# ngh-ioctl.net
KiCad netlist of a schematic drawn in Altium Designer
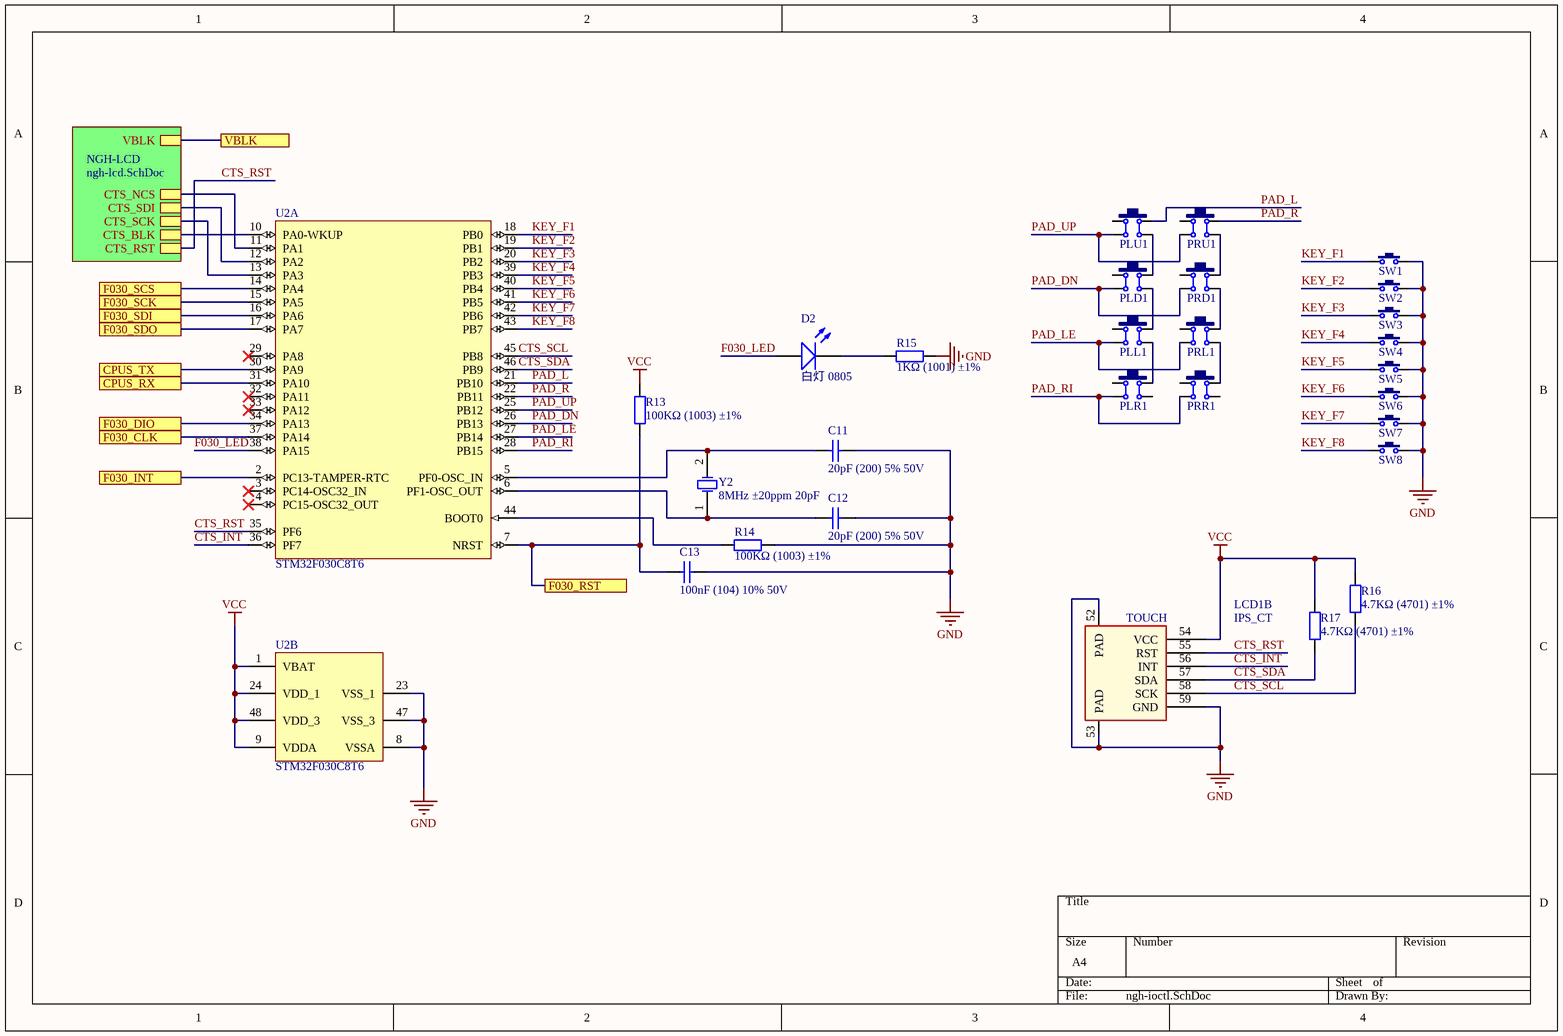
[diagram p0: ngh-ioctl.SchDoc]

(export (version "E")
  (design (tool "Eeschema 10.0.6"))
  (components
    (comp (ref "C11")
      (value "20pF (200) 5% 50V")
      (footprint "0603_C")
      (description "贴片电容")
      (libsource (lib "Miscellaneous Devices LC") (part "0603 20pF (200) 5% 50V"))
    )
    (comp (ref "C12")
      (value "20pF (200) 5% 50V")
      (footprint "0603_C")
      (description "贴片电容")
      (libsource (lib "Miscellaneous Devices LC") (part "0603 20pF (200) 5% 50V"))
    )
    (comp (ref "C13")
      (value "100nF (104) 10% 50V")
      (footprint "0603_C")
      (description "贴片电容")
      (libsource (lib "Miscellaneous Devices LC") (part "0603 100nF (104) 10% 50V"))
    )
    (comp (ref "D2")
      (value "白灯 0805")
      (footprint "0805_LED_S1")
      (description "发光二极管")
      (libsource (lib "Miscellaneous Devices LC") (part "0805 白灯"))
    )
    (comp (ref "LCD1") (value "IPS_CT") (footprint "IPS_CT") (libsource (lib "Tiky_IPS_CT") (part "IPS_CT")))
    (comp (ref "PLD1")
      (value "12x12x5")
      (footprint "TSW SMD-12*12*6")
      (description "贴片12x12轻触开关")
      (fields (field (name "版权归属") "源创客"))
      (libsource (lib "5.1   - 按键-开关") (part "TSW SMD-12x12"))
    )
    (comp (ref "PLL1")
      (value "12x12x5")
      (footprint "TSW SMD-12*12*6")
      (description "贴片12x12轻触开关")
      (fields (field (name "版权归属") "源创客"))
      (libsource (lib "5.1   - 按键-开关") (part "TSW SMD-12x12"))
    )
    (comp (ref "PLR1")
      (value "12x12x5")
      (footprint "TSW SMD-12*12*6")
      (description "贴片12x12轻触开关")
      (fields (field (name "版权归属") "源创客"))
      (libsource (lib "5.1   - 按键-开关") (part "TSW SMD-12x12"))
    )
    (comp (ref "PLU1")
      (value "12x12x5")
      (footprint "TSW SMD-12*12*6")
      (description "贴片12x12轻触开关")
      (fields (field (name "版权归属") "源创客"))
      (libsource (lib "5.1   - 按键-开关") (part "TSW SMD-12x12"))
    )
    (comp (ref "PRD1")
      (value "12x12x5")
      (footprint "TSW SMD-12*12*6")
      (description "贴片12x12轻触开关")
      (fields (field (name "版权归属") "源创客"))
      (libsource (lib "5.1   - 按键-开关") (part "TSW SMD-12x12"))
    )
    (comp (ref "PRL1")
      (value "12x12x5")
      (footprint "TSW SMD-12*12*6")
      (description "贴片12x12轻触开关")
      (fields (field (name "版权归属") "源创客"))
      (libsource (lib "5.1   - 按键-开关") (part "TSW SMD-12x12"))
    )
    (comp (ref "PRR1")
      (value "12x12x5")
      (footprint "TSW SMD-12*12*6")
      (description "贴片12x12轻触开关")
      (fields (field (name "版权归属") "源创客"))
      (libsource (lib "5.1   - 按键-开关") (part "TSW SMD-12x12"))
    )
    (comp (ref "PRU1")
      (value "12x12x5")
      (footprint "TSW SMD-12*12*6")
      (description "贴片12x12轻触开关")
      (fields (field (name "版权归属") "源创客"))
      (libsource (lib "5.1   - 按键-开关") (part "TSW SMD-12x12"))
    )
    (comp (ref "R13")
      (value "100KΩ (1003) ±1%")
      (footprint "0603_R")
      (description "贴片电阻")
      (libsource (lib "") (part "0603 100KΩ (1003) 1%_1"))
    )
    (comp (ref "R14")
      (value "100KΩ (1003) ±1%")
      (footprint "0603_R")
      (description "贴片电阻")
      (libsource (lib "Miscellaneous Devices LC") (part "0603 100KΩ (1003) 1%"))
    )
    (comp (ref "R15")
      (value "1KΩ (1001) ±1%")
      (footprint "0603_R")
      (description "贴片电阻")
      (libsource (lib "Miscellaneous Devices LC") (part "0603 1KΩ (1001) 1%"))
    )
    (comp (ref "R16")
      (value "4.7KΩ (4701) ±1%")
      (footprint "0603_R")
      (description "贴片电阻")
      (libsource (lib "Miscellaneous Devices LC") (part "0603 4.7KΩ (4701) 1%"))
    )
    (comp (ref "R17")
      (value "4.7KΩ (4701) ±1%")
      (footprint "0603_R")
      (description "贴片电阻")
      (libsource (lib "Miscellaneous Devices LC") (part "0603 4.7KΩ (4701) 1%"))
    )
    (comp (ref "SW1")
      (value "3x6x5")
      (footprint "TSW SMD-3*6*4.3")
      (description "3x6轻触开关")
      (fields (field (name "版权归属") "源创客"))
      (libsource (lib "5.1   - 按键-开关") (part "TSW 3x6"))
    )
    (comp (ref "SW2")
      (value "3x6x5")
      (footprint "TSW SMD-3*6*4.3")
      (description "3x6轻触开关")
      (fields (field (name "版权归属") "源创客"))
      (libsource (lib "5.1   - 按键-开关") (part "TSW 3x6"))
    )
    (comp (ref "SW3")
      (value "3x6x5")
      (footprint "TSW SMD-3*6*4.3")
      (description "3x6轻触开关")
      (fields (field (name "版权归属") "源创客"))
      (libsource (lib "5.1   - 按键-开关") (part "TSW 3x6"))
    )
    (comp (ref "SW4")
      (value "3x6x5")
      (footprint "TSW SMD-3*6*4.3")
      (description "3x6轻触开关")
      (fields (field (name "版权归属") "源创客"))
      (libsource (lib "5.1   - 按键-开关") (part "TSW 3x6"))
    )
    (comp (ref "SW5")
      (value "3x6x5")
      (footprint "TSW SMD-3*6*4.3")
      (description "3x6轻触开关")
      (fields (field (name "版权归属") "源创客"))
      (libsource (lib "5.1   - 按键-开关") (part "TSW 3x6"))
    )
    (comp (ref "SW6")
      (value "3x6x5")
      (footprint "TSW SMD-3*6*4.3")
      (description "3x6轻触开关")
      (fields (field (name "版权归属") "源创客"))
      (libsource (lib "5.1   - 按键-开关") (part "TSW 3x6"))
    )
    (comp (ref "SW7")
      (value "3x6x5")
      (footprint "TSW SMD-3*6*4.3")
      (description "3x6轻触开关")
      (fields (field (name "版权归属") "源创客"))
      (libsource (lib "5.1   - 按键-开关") (part "TSW 3x6"))
    )
    (comp (ref "SW8")
      (value "3x6x5")
      (footprint "TSW SMD-3*6*4.3")
      (description "3x6轻触开关")
      (fields (field (name "版权归属") "源创客"))
      (libsource (lib "5.1   - 按键-开关") (part "TSW 3x6"))
    )
    (comp (ref "U2")
      (value "STM32F030C8T6")
      (footprint "LQFP-48_7x7x05P")
      (description "ARM")
      (libsource (lib "STM32F030C8") (part "STM32F030C8T6"))
    )
    (comp (ref "Y2")
      (value "8MHz ±20ppm 20pF")
      (footprint "SMD-5032_2P")
      (description "贴片晶振")
      (libsource (lib "Miscellaneous Devices LC") (part "SMD-5032_2P 8MHz 20ppm 20pF"))
    )
  )
  (nets
    (net (code "1") (name "/CPUS_RX") (class "Default")
      (node (ref "U2") (pin "31") (pinfunction "PA10_31") (pintype "bidirectional"))
    )
    (net (code "2") (name "/CPUS_TX") (class "Default")
      (node (ref "U2") (pin "30") (pinfunction "PA9_30") (pintype "bidirectional"))
    )
    (net (code "3") (name "/CTS_BLK") (class "Default")
      (node (ref "U2") (pin "10") (pinfunction "PA0-WKUP_10") (pintype "bidirectional"))
    )
    (net (code "4") (name "/CTS_INT") (class "Default")
      (node (ref "LCD1") (pin "56") (pinfunction "INT_56") (pintype "passive"))
      (node (ref "U2") (pin "36") (pinfunction "PF7_36") (pintype "bidirectional"))
    )
    (net (code "5") (name "/CTS_NCS") (class "Default")
      (node (ref "U2") (pin "11") (pinfunction "PA1_11") (pintype "bidirectional"))
    )
    (net (code "6") (name "/CTS_RST") (class "Default")
      (node (ref "LCD1") (pin "55") (pinfunction "RST_55") (pintype "passive"))
      (node (ref "U2") (pin "35") (pinfunction "PF6_35") (pintype "bidirectional"))
    )
    (net (code "7") (name "/CTS_SCK") (class "Default")
      (node (ref "U2") (pin "13") (pinfunction "PA3_13") (pintype "bidirectional"))
    )
    (net (code "8") (name "/CTS_SCL") (class "Default")
      (node (ref "LCD1") (pin "58") (pinfunction "SCK_58") (pintype "passive"))
      (node (ref "R16") (pin "1") (pinfunction "1_1") (pintype "passive"))
      (node (ref "U2") (pin "45") (pinfunction "PB8_45") (pintype "bidirectional"))
    )
    (net (code "9") (name "/CTS_SDA") (class "Default")
      (node (ref "LCD1") (pin "57") (pinfunction "SDA_57") (pintype "passive"))
      (node (ref "R17") (pin "1") (pinfunction "1_1") (pintype "passive"))
      (node (ref "U2") (pin "46") (pinfunction "PB9_46") (pintype "bidirectional"))
    )
    (net (code "10") (name "/CTS_SDI") (class "Default")
      (node (ref "U2") (pin "12") (pinfunction "PA2_12") (pintype "bidirectional"))
    )
    (net (code "11") (name "/F030_CLK") (class "Default")
      (node (ref "U2") (pin "37") (pinfunction "PA14_37") (pintype "bidirectional"))
    )
    (net (code "12") (name "/F030_DIO") (class "Default")
      (node (ref "U2") (pin "34") (pinfunction "PA13_34") (pintype "bidirectional"))
    )
    (net (code "13") (name "/F030_INT") (class "Default")
      (node (ref "U2") (pin "2") (pinfunction "PC13-TAMPER-RTC_2") (pintype "bidirectional"))
    )
    (net (code "14") (name "/F030_LED") (class "Default")
      (node (ref "D2") (pin "A") (pinfunction "A_A") (pintype "passive"))
      (node (ref "U2") (pin "38") (pinfunction "PA15_38") (pintype "bidirectional"))
    )
    (net (code "15") (name "/F030_RST") (class "Default")
      (node (ref "C13") (pin "2") (pinfunction "2_2") (pintype "passive"))
      (node (ref "R13") (pin "1") (pinfunction "1_1") (pintype "passive"))
      (node (ref "U2") (pin "7") (pinfunction "NRST_7") (pintype "bidirectional"))
    )
    (net (code "16") (name "/F030_SCK") (class "Default")
      (node (ref "U2") (pin "15") (pinfunction "PA5_15") (pintype "bidirectional"))
    )
    (net (code "17") (name "/F030_SCS") (class "Default")
      (node (ref "U2") (pin "14") (pinfunction "PA4_14") (pintype "bidirectional"))
    )
    (net (code "18") (name "/F030_SDI") (class "Default")
      (node (ref "U2") (pin "16") (pinfunction "PA6_16") (pintype "bidirectional"))
    )
    (net (code "19") (name "/F030_SDO") (class "Default")
      (node (ref "U2") (pin "17") (pinfunction "PA7_17") (pintype "bidirectional"))
    )
    (net (code "20") (name "/KEY_F1") (class "Default")
      (node (ref "SW1") (pin "1") (pinfunction "1_1") (pintype "passive"))
      (node (ref "U2") (pin "18") (pinfunction "PB0_18") (pintype "bidirectional"))
    )
    (net (code "21") (name "/KEY_F2") (class "Default")
      (node (ref "SW2") (pin "1") (pinfunction "1_1") (pintype "passive"))
      (node (ref "U2") (pin "19") (pinfunction "PB1_19") (pintype "bidirectional"))
    )
    (net (code "22") (name "/KEY_F3") (class "Default")
      (node (ref "SW3") (pin "1") (pinfunction "1_1") (pintype "passive"))
      (node (ref "U2") (pin "20") (pinfunction "PB2_20") (pintype "bidirectional"))
    )
    (net (code "23") (name "/KEY_F4") (class "Default")
      (node (ref "SW4") (pin "1") (pinfunction "1_1") (pintype "passive"))
      (node (ref "U2") (pin "39") (pinfunction "PB3_39") (pintype "bidirectional"))
    )
    (net (code "24") (name "/KEY_F5") (class "Default")
      (node (ref "SW5") (pin "1") (pinfunction "1_1") (pintype "passive"))
      (node (ref "U2") (pin "40") (pinfunction "PB4_40") (pintype "bidirectional"))
    )
    (net (code "25") (name "/KEY_F6") (class "Default")
      (node (ref "SW6") (pin "1") (pinfunction "1_1") (pintype "passive"))
      (node (ref "U2") (pin "41") (pinfunction "PB5_41") (pintype "bidirectional"))
    )
    (net (code "26") (name "/KEY_F7") (class "Default")
      (node (ref "SW7") (pin "1") (pinfunction "1_1") (pintype "passive"))
      (node (ref "U2") (pin "42") (pinfunction "PB6_42") (pintype "bidirectional"))
    )
    (net (code "27") (name "/KEY_F8") (class "Default")
      (node (ref "SW8") (pin "1") (pinfunction "1_1") (pintype "passive"))
      (node (ref "U2") (pin "43") (pinfunction "PB7_43") (pintype "bidirectional"))
    )
    (net (code "28") (name "/PAD_DN") (class "Default")
      (node (ref "PLD1") (pin "4") (pinfunction "4_4") (pintype "passive"))
      (node (ref "PRD1") (pin "4") (pinfunction "4_4") (pintype "passive"))
      (node (ref "U2") (pin "26") (pinfunction "PB13_26") (pintype "bidirectional"))
    )
    (net (code "29") (name "/PAD_L") (class "Default")
      (node (ref "PLU1") (pin "2") (pinfunction "2_2") (pintype "passive"))
      (node (ref "U2") (pin "21") (pinfunction "PB10_21") (pintype "bidirectional"))
    )
    (net (code "30") (name "/PAD_LE") (class "Default")
      (node (ref "PLL1") (pin "4") (pinfunction "4_4") (pintype "passive"))
      (node (ref "PRL1") (pin "4") (pinfunction "4_4") (pintype "passive"))
      (node (ref "U2") (pin "27") (pinfunction "PB14_27") (pintype "bidirectional"))
    )
    (net (code "31") (name "/PAD_R") (class "Default")
      (node (ref "PRU1") (pin "2") (pinfunction "2_2") (pintype "passive"))
      (node (ref "U2") (pin "22") (pinfunction "PB11_22") (pintype "bidirectional"))
    )
    (net (code "32") (name "/PAD_RI") (class "Default")
      (node (ref "PLR1") (pin "4") (pinfunction "4_4") (pintype "passive"))
      (node (ref "PRR1") (pin "4") (pinfunction "4_4") (pintype "passive"))
      (node (ref "U2") (pin "28") (pinfunction "PB15_28") (pintype "bidirectional"))
    )
    (net (code "33") (name "/PAD_UP") (class "Default")
      (node (ref "PLU1") (pin "4") (pinfunction "4_4") (pintype "passive"))
      (node (ref "PRU1") (pin "4") (pinfunction "4_4") (pintype "passive"))
      (node (ref "U2") (pin "25") (pinfunction "PB12_25") (pintype "bidirectional"))
    )
    (net (code "35") (name "GND") (class "Default")
      (node (ref "C11") (pin "2") (pinfunction "2_2") (pintype "passive"))
      (node (ref "C12") (pin "2") (pinfunction "2_2") (pintype "passive"))
      (node (ref "C13") (pin "1") (pinfunction "1_1") (pintype "passive"))
      (node (ref "LCD1") (pin "52") (pinfunction "PAD_52") (pintype "passive"))
      (node (ref "LCD1") (pin "53") (pinfunction "PAD_53") (pintype "passive"))
      (node (ref "LCD1") (pin "59") (pinfunction "GND_59") (pintype "passive"))
      (node (ref "R14") (pin "2") (pinfunction "2_2") (pintype "passive"))
      (node (ref "R15") (pin "2") (pinfunction "2_2") (pintype "passive"))
      (node (ref "SW1") (pin "2") (pinfunction "2_2") (pintype "passive"))
      (node (ref "SW2") (pin "2") (pinfunction "2_2") (pintype "passive"))
      (node (ref "SW3") (pin "2") (pinfunction "2_2") (pintype "passive"))
      (node (ref "SW4") (pin "2") (pinfunction "2_2") (pintype "passive"))
      (node (ref "SW5") (pin "2") (pinfunction "2_2") (pintype "passive"))
      (node (ref "SW6") (pin "2") (pinfunction "2_2") (pintype "passive"))
      (node (ref "SW7") (pin "2") (pinfunction "2_2") (pintype "passive"))
      (node (ref "SW8") (pin "2") (pinfunction "2_2") (pintype "passive"))
      (node (ref "U2") (pin "23") (pinfunction "VSS_1_23") (pintype "power_in"))
      (node (ref "U2") (pin "47") (pinfunction "VSS_3_47") (pintype "power_in"))
      (node (ref "U2") (pin "8") (pinfunction "VSSA_8") (pintype "power_in"))
    )
    (net (code "36") (name "Net-(D2-PadK)") (class "Default")
      (node (ref "D2") (pin "K") (pinfunction "K_K") (pintype "passive"))
      (node (ref "R15") (pin "1") (pinfunction "1_1") (pintype "passive"))
    )
    (net (code "37") (name "Net-(PLD1-Pad2)") (class "Default")
      (node (ref "PLD1") (pin "2") (pinfunction "2_2") (pintype "passive"))
      (node (ref "PLU1") (pin "3") (pinfunction "3_3") (pintype "passive"))
    )
    (net (code "38") (name "Net-(PLD1-Pad3)") (class "Default")
      (node (ref "PLD1") (pin "3") (pinfunction "3_3") (pintype "passive"))
      (node (ref "PLL1") (pin "2") (pinfunction "2_2") (pintype "passive"))
    )
    (net (code "39") (name "Net-(PLL1-Pad3)") (class "Default")
      (node (ref "PLL1") (pin "3") (pinfunction "3_3") (pintype "passive"))
      (node (ref "PLR1") (pin "2") (pinfunction "2_2") (pintype "passive"))
    )
    (net (code "40") (name "Net-(PRD1-Pad2)") (class "Default")
      (node (ref "PRD1") (pin "2") (pinfunction "2_2") (pintype "passive"))
      (node (ref "PRU1") (pin "3") (pinfunction "3_3") (pintype "passive"))
    )
    (net (code "41") (name "Net-(PRD1-Pad3)") (class "Default")
      (node (ref "PRD1") (pin "3") (pinfunction "3_3") (pintype "passive"))
      (node (ref "PRL1") (pin "2") (pinfunction "2_2") (pintype "passive"))
    )
    (net (code "42") (name "Net-(PRL1-Pad3)") (class "Default")
      (node (ref "PRL1") (pin "3") (pinfunction "3_3") (pintype "passive"))
      (node (ref "PRR1") (pin "2") (pinfunction "2_2") (pintype "passive"))
    )
    (net (code "43") (name "Net-(U2A-BOOT0)") (class "Default")
      (node (ref "R14") (pin "1") (pinfunction "1_1") (pintype "passive"))
      (node (ref "U2") (pin "44") (pinfunction "BOOT0_44") (pintype "input"))
    )
    (net (code "44") (name "Net-(U2A-PF0-OSC_IN)") (class "Default")
      (node (ref "C11") (pin "1") (pinfunction "1_1") (pintype "passive"))
      (node (ref "U2") (pin "5") (pinfunction "PF0-OSC_IN_5") (pintype "bidirectional"))
      (node (ref "Y2") (pin "2") (pinfunction "OSC2_2") (pintype "passive"))
    )
    (net (code "45") (name "Net-(U2A-PF1-OSC_OUT)") (class "Default")
      (node (ref "C12") (pin "1") (pinfunction "1_1") (pintype "passive"))
      (node (ref "U2") (pin "6") (pinfunction "PF1-OSC_OUT_6") (pintype "bidirectional"))
      (node (ref "Y2") (pin "1") (pinfunction "OSC1_1") (pintype "passive"))
    )
    (net (code "46") (name "VCC") (class "Default")
      (node (ref "LCD1") (pin "54") (pinfunction "VCC_54") (pintype "passive"))
      (node (ref "R13") (pin "2") (pinfunction "2_2") (pintype "passive"))
      (node (ref "R16") (pin "2") (pinfunction "2_2") (pintype "passive"))
      (node (ref "R17") (pin "2") (pinfunction "2_2") (pintype "passive"))
      (node (ref "U2") (pin "1") (pinfunction "VBAT_1") (pintype "power_in"))
      (node (ref "U2") (pin "24") (pinfunction "VDD_1_24") (pintype "power_in"))
      (node (ref "U2") (pin "48") (pinfunction "VDD_3_48") (pintype "power_in"))
      (node (ref "U2") (pin "9") (pinfunction "VDDA_9") (pintype "power_in"))
    )
    (net (code "47") (name "unconnected-(PLD1-Pad1)") (class "Default")
      (node (ref "PLD1") (pin "1") (pinfunction "1_1") (pintype "passive"))
    )
    (net (code "48") (name "unconnected-(PLL1-Pad1)") (class "Default")
      (node (ref "PLL1") (pin "1") (pinfunction "1_1") (pintype "passive"))
    )
    (net (code "49") (name "unconnected-(PLR1-Pad1)") (class "Default")
      (node (ref "PLR1") (pin "1") (pinfunction "1_1") (pintype "passive"))
    )
    (net (code "50") (name "unconnected-(PLR1-Pad3)") (class "Default")
      (node (ref "PLR1") (pin "3") (pinfunction "3_3") (pintype "passive"))
    )
    (net (code "51") (name "unconnected-(PLU1-Pad1)") (class "Default")
      (node (ref "PLU1") (pin "1") (pinfunction "1_1") (pintype "passive"))
    )
    (net (code "52") (name "unconnected-(PRD1-Pad1)") (class "Default")
      (node (ref "PRD1") (pin "1") (pinfunction "1_1") (pintype "passive"))
    )
    (net (code "53") (name "unconnected-(PRL1-Pad1)") (class "Default")
      (node (ref "PRL1") (pin "1") (pinfunction "1_1") (pintype "passive"))
    )
    (net (code "54") (name "unconnected-(PRR1-Pad1)") (class "Default")
      (node (ref "PRR1") (pin "1") (pinfunction "1_1") (pintype "passive"))
    )
    (net (code "55") (name "unconnected-(PRR1-Pad3)") (class "Default")
      (node (ref "PRR1") (pin "3") (pinfunction "3_3") (pintype "passive"))
    )
    (net (code "56") (name "unconnected-(PRU1-Pad1)") (class "Default")
      (node (ref "PRU1") (pin "1") (pinfunction "1_1") (pintype "passive"))
    )
    (net (code "57") (name "unconnected-(U2A-PA8-Pad29)") (class "Default")
      (node (ref "U2") (pin "29") (pinfunction "PA8_29") (pintype "bidirectional+no_connect"))
    )
    (net (code "58") (name "unconnected-(U2A-PA11-Pad32)") (class "Default")
      (node (ref "U2") (pin "32") (pinfunction "PA11_32") (pintype "bidirectional+no_connect"))
    )
    (net (code "59") (name "unconnected-(U2A-PA12-Pad33)") (class "Default")
      (node (ref "U2") (pin "33") (pinfunction "PA12_33") (pintype "bidirectional+no_connect"))
    )
    (net (code "60") (name "unconnected-(U2A-PC14-OSC32_IN-Pad3)") (class "Default")
      (node (ref "U2") (pin "3") (pinfunction "PC14-OSC32_IN_3") (pintype "bidirectional+no_connect"))
    )
    (net (code "61") (name "unconnected-(U2A-PC15-OSC32_OUT-Pad4)") (class "Default")
      (node (ref "U2") (pin "4") (pinfunction "PC15-OSC32_OUT_4") (pintype "bidirectional+no_connect"))
    )
  )
)
